# BSPD_System.net
KiCad netlist of a schematic drawn in Altium Designer
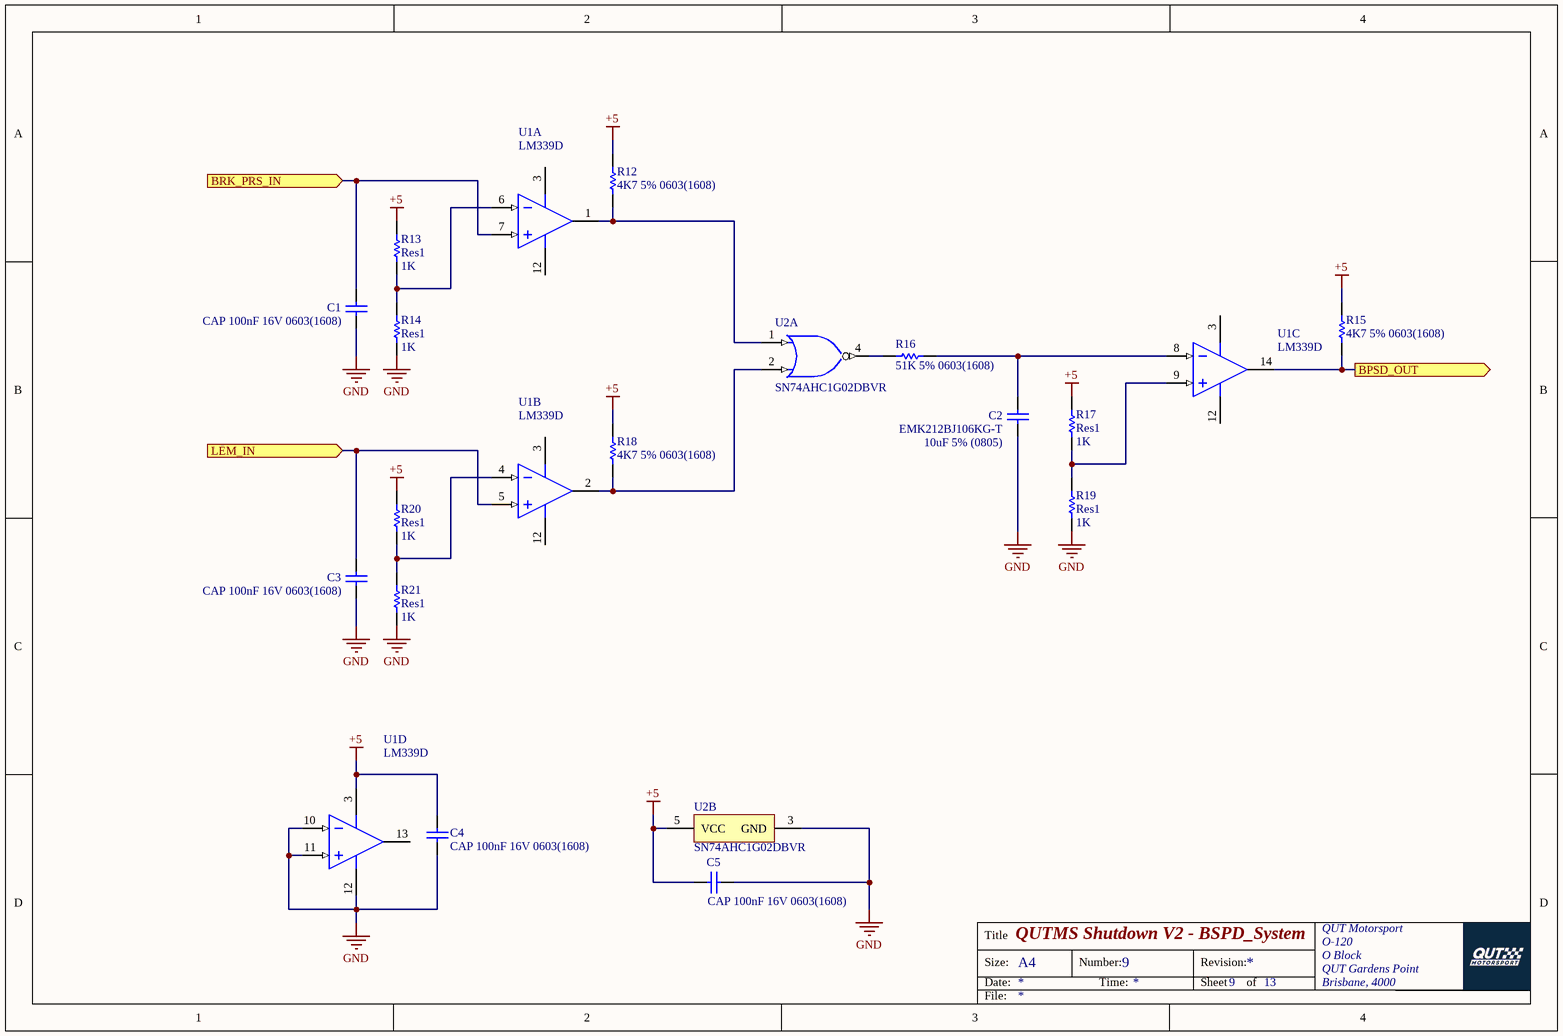
[diagram p0: BSPD_System.SchDoc]

(export (version "E")
  (design (tool "Eeschema 10.0.6"))
  (components
    (comp (ref "C1")
      (value "CAP 100nF 16V 0603(1608)")
      (footprint "CAPC0603(1608)100_M")
      (description "CAP 100nF 16V ±5% 0603 (1608 Metric) Thickness 1mm SMD")
      (fields (field (name "TOLERANCE") "Â±5%"))
      (libsource (lib "Altium Content Vault") (part "CAP"))
    )
    (comp (ref "C2")
      (value "EMK212BJ106KG-T")
      (footprint "CAPC2013X135X50ML10T25")
      (description "Chip Capacitor, 10 uF, +/- 10%, 16 V, -25 to 85 degC, 0805 (2012 Metric), RoHS, Tape and Reel")
      (fields
        (field (name "TOLERANCE") "±10%")
        (field (name "PCN PART NUMBER") "X5R,X7RDielectrics23/Jan/2008")
      )
      (libsource (lib "Altium Content Vault") (part "CAP-NP-2"))
    )
    (comp (ref "C3")
      (value "CAP 100nF 16V 0603(1608)")
      (footprint "CAPC0603(1608)100_M")
      (description "CAP 100nF 16V ±5% 0603 (1608 Metric) Thickness 1mm SMD")
      (fields (field (name "TOLERANCE") "Â±5%"))
      (libsource (lib "Altium Content Vault") (part "CAP"))
    )
    (comp (ref "C4")
      (value "CAP 100nF 16V 0603(1608)")
      (footprint "CAPC0603(1608)100_M")
      (description "CAP 100nF 16V ±5% 0603 (1608 Metric) Thickness 1mm SMD")
      (fields (field (name "TOLERANCE") "Â±5%"))
      (libsource (lib "Altium Content Vault") (part "CAP"))
    )
    (comp (ref "C5")
      (value "CAP 100nF 16V 0603(1608)")
      (footprint "CAPC0603(1608)100_M")
      (description "CAP 100nF 16V ±5% 0603 (1608 Metric) Thickness 1mm SMD")
      (fields (field (name "TOLERANCE") "Â±5%"))
      (libsource (lib "Altium Content Vault") (part "CAP"))
    )
    (comp (ref "R12")
      (value "4K7 5% 0603(1608)")
      (footprint "RESC0603(1608)_N")
      (description "4K7 0.1W 5% 0603 (1608 Metric)  SMD")
      (fields (field (name "TOLERANCE") "5 %") (field (name "POWER") "0.1 W"))
      (libsource (lib "Altium Content Vault") (part "RES"))
    )
    (comp (ref "R13")
      (value "Res1")
      (footprint "AXIAL-0.3")
      (description "Resistor")
      (fields (field (name "ALTIUM_VALUE") "1K") (field (name "PUBLISHER") "Altium Limited"))
      (libsource (lib "Miscellaneous Devices") (part "Res1"))
    )
    (comp (ref "R14")
      (value "Res1")
      (footprint "AXIAL-0.3")
      (description "Resistor")
      (fields (field (name "ALTIUM_VALUE") "1K") (field (name "PUBLISHER") "Altium Limited"))
      (libsource (lib "Miscellaneous Devices") (part "Res1"))
    )
    (comp (ref "R15")
      (value "4K7 5% 0603(1608)")
      (footprint "RESC0603(1608)_N")
      (description "4K7 0.1W 5% 0603 (1608 Metric)  SMD")
      (fields (field (name "TOLERANCE") "5 %") (field (name "POWER") "0.1 W"))
      (libsource (lib "Altium Content Vault") (part "RES"))
    )
    (comp (ref "R16")
      (value "51K 5% 0603(1608)")
      (footprint "RESC0603(1608)_M")
      (description "51K 0.1W 5% 0603 (1608 Metric)  SMD")
      (fields (field (name "POWER") "0.1 W") (field (name "TOLERANCE") "5 %"))
      (libsource (lib "Altium Content Vault") (part "RES"))
    )
    (comp (ref "R17")
      (value "Res1")
      (footprint "AXIAL-0.3")
      (description "Resistor")
      (fields (field (name "ALTIUM_VALUE") "1K") (field (name "PUBLISHER") "Altium Limited"))
      (libsource (lib "Miscellaneous Devices") (part "Res1"))
    )
    (comp (ref "R18")
      (value "4K7 5% 0603(1608)")
      (footprint "RESC0603(1608)_N")
      (description "4K7 0.1W 5% 0603 (1608 Metric)  SMD")
      (fields (field (name "TOLERANCE") "5 %") (field (name "POWER") "0.1 W"))
      (libsource (lib "Altium Content Vault") (part "RES"))
    )
    (comp (ref "R19")
      (value "Res1")
      (footprint "AXIAL-0.3")
      (description "Resistor")
      (fields (field (name "ALTIUM_VALUE") "1K") (field (name "PUBLISHER") "Altium Limited"))
      (libsource (lib "Miscellaneous Devices") (part "Res1"))
    )
    (comp (ref "R20")
      (value "Res1")
      (footprint "AXIAL-0.3")
      (description "Resistor")
      (fields (field (name "ALTIUM_VALUE") "1K") (field (name "PUBLISHER") "Altium Limited"))
      (libsource (lib "Miscellaneous Devices") (part "Res1"))
    )
    (comp (ref "R21")
      (value "Res1")
      (footprint "AXIAL-0.3")
      (description "Resistor")
      (fields (field (name "ALTIUM_VALUE") "1K") (field (name "PUBLISHER") "Altium Limited"))
      (libsource (lib "Miscellaneous Devices") (part "Res1"))
    )
    (comp (ref "U1")
      (value "LM339D")
      (footprint "D0014A_L")
      (fields (field (name "MANUFACTURER") "Texas Instruments"))
      (libsource (lib "Altium Content Vault") (part "TI-LMXXXX14"))
    )
    (comp (ref "U2")
      (value "SN74AHC1G02DBVR")
      (footprint "DBV0005A_L")
      (description "Single 2-Input Positive-NOR Gate, DBV0005A, LARGE T&R")
      (fields
        (field (name "MANUFACTURER") "Texas Instruments")
        (field (name "GENERIC PART NUMBER") "SN74AHC1G02")
      )
      (libsource (lib "Altium Content Vault") (part "TI-SN74XXX1X02-5"))
    )
  )
  (nets
    (net (code "1") (name "+5") (class "Default")
      (node (ref "C4") (pin "2") (pinfunction "2_2") (pintype "passive"))
      (node (ref "C5") (pin "1") (pinfunction "1_1") (pintype "passive"))
      (node (ref "R12") (pin "2") (pinfunction "2_2") (pintype "passive"))
      (node (ref "R13") (pin "1") (pinfunction "1_1") (pintype "passive"))
      (node (ref "R15") (pin "2") (pinfunction "2_2") (pintype "passive"))
      (node (ref "R17") (pin "2") (pinfunction "2_2") (pintype "passive"))
      (node (ref "R18") (pin "2") (pinfunction "2_2") (pintype "passive"))
      (node (ref "R20") (pin "2") (pinfunction "2_2") (pintype "passive"))
      (node (ref "U1") (pin "3") (pinfunction "VCC_3") (pintype "power_in"))
      (node (ref "U2") (pin "5") (pinfunction "VCC_5") (pintype "power_in"))
    )
    (net (code "2") (name "/BPSD_OUT") (class "Default")
      (node (ref "R15") (pin "1") (pinfunction "1_1") (pintype "passive"))
      (node (ref "U1") (pin "14") (pinfunction "OUT3_14") (pintype "open_collector"))
    )
    (net (code "3") (name "/BRK_PRS_IN") (class "Default")
      (node (ref "C1") (pin "2") (pinfunction "2_2") (pintype "passive"))
      (node (ref "U1") (pin "7") (pinfunction "IN1+_7") (pintype "input"))
    )
    (net (code "4") (name "/LEM_IN") (class "Default")
      (node (ref "C3") (pin "2") (pinfunction "2_2") (pintype "passive"))
      (node (ref "U1") (pin "5") (pinfunction "IN2+_5") (pintype "input"))
    )
    (net (code "5") (name "GND") (class "Default")
      (node (ref "C1") (pin "1") (pinfunction "1_1") (pintype "passive"))
      (node (ref "C2") (pin "1") (pinfunction "1_1") (pintype "passive"))
      (node (ref "C3") (pin "1") (pinfunction "1_1") (pintype "passive"))
      (node (ref "C4") (pin "1") (pinfunction "1_1") (pintype "passive"))
      (node (ref "C5") (pin "2") (pinfunction "2_2") (pintype "passive"))
      (node (ref "R14") (pin "2") (pinfunction "2_2") (pintype "passive"))
      (node (ref "R19") (pin "1") (pinfunction "1_1") (pintype "passive"))
      (node (ref "R21") (pin "1") (pinfunction "1_1") (pintype "passive"))
      (node (ref "U1") (pin "10") (pinfunction "IN4-_10") (pintype "input"))
      (node (ref "U1") (pin "11") (pinfunction "IN4+_11") (pintype "input"))
      (node (ref "U1") (pin "12") (pinfunction "GND_12") (pintype "power_in"))
      (node (ref "U2") (pin "3") (pinfunction "GND_3") (pintype "power_in"))
    )
    (net (code "6") (name "Net-(U1A-IN1-)") (class "Default")
      (node (ref "R13") (pin "2") (pinfunction "2_2") (pintype "passive"))
      (node (ref "R14") (pin "1") (pinfunction "1_1") (pintype "passive"))
      (node (ref "U1") (pin "6") (pinfunction "IN1-_6") (pintype "input"))
    )
    (net (code "7") (name "Net-(U1A-OUT1)") (class "Default")
      (node (ref "R12") (pin "1") (pinfunction "1_1") (pintype "passive"))
      (node (ref "U1") (pin "1") (pinfunction "OUT1_1") (pintype "open_collector"))
      (node (ref "U2") (pin "1") (pinfunction "A_1") (pintype "input"))
    )
    (net (code "8") (name "Net-(U1B-IN2-)") (class "Default")
      (node (ref "R20") (pin "1") (pinfunction "1_1") (pintype "passive"))
      (node (ref "R21") (pin "2") (pinfunction "2_2") (pintype "passive"))
      (node (ref "U1") (pin "4") (pinfunction "IN2-_4") (pintype "input"))
    )
    (net (code "9") (name "Net-(U1B-OUT2)") (class "Default")
      (node (ref "R18") (pin "1") (pinfunction "1_1") (pintype "passive"))
      (node (ref "U1") (pin "2") (pinfunction "OUT2_2") (pintype "open_collector"))
      (node (ref "U2") (pin "2") (pinfunction "B_2") (pintype "input"))
    )
    (net (code "10") (name "Net-(U1C-IN3+)") (class "Default")
      (node (ref "R17") (pin "1") (pinfunction "1_1") (pintype "passive"))
      (node (ref "R19") (pin "2") (pinfunction "2_2") (pintype "passive"))
      (node (ref "U1") (pin "9") (pinfunction "IN3+_9") (pintype "input"))
    )
    (net (code "11") (name "Net-(U1C-IN3-)") (class "Default")
      (node (ref "C2") (pin "2") (pinfunction "2_2") (pintype "passive"))
      (node (ref "R16") (pin "2") (pinfunction "2_2") (pintype "passive"))
      (node (ref "U1") (pin "8") (pinfunction "IN3-_8") (pintype "input"))
    )
    (net (code "12") (name "Net-(U2A-Y)") (class "Default")
      (node (ref "R16") (pin "1") (pinfunction "1_1") (pintype "passive"))
      (node (ref "U2") (pin "4") (pinfunction "Y_4") (pintype "output"))
    )
    (net (code "13") (name "unconnected-(U1A-GND-Pad12)") (class "Default")
      (node (ref "U1") (pin "12") (pinfunction "GND_12") (pintype "power_in"))
    )
    (net (code "14") (name "unconnected-(U1A-VCC-Pad3)") (class "Default")
      (node (ref "U1") (pin "3") (pinfunction "VCC_3") (pintype "power_in"))
    )
    (net (code "15") (name "unconnected-(U1B-GND-Pad12)") (class "Default")
      (node (ref "U1") (pin "12") (pinfunction "GND_12") (pintype "power_in"))
    )
    (net (code "16") (name "unconnected-(U1B-VCC-Pad3)") (class "Default")
      (node (ref "U1") (pin "3") (pinfunction "VCC_3") (pintype "power_in"))
    )
    (net (code "17") (name "unconnected-(U1C-GND-Pad12)") (class "Default")
      (node (ref "U1") (pin "12") (pinfunction "GND_12") (pintype "power_in"))
    )
    (net (code "18") (name "unconnected-(U1C-VCC-Pad3)") (class "Default")
      (node (ref "U1") (pin "3") (pinfunction "VCC_3") (pintype "power_in"))
    )
    (net (code "19") (name "unconnected-(U1D-OUT4-Pad13)") (class "Default")
      (node (ref "U1") (pin "13") (pinfunction "OUT4_13") (pintype "open_collector"))
    )
  )
)
